# LED_Cube.net
KiCad netlist of a schematic drawn in EAGLE
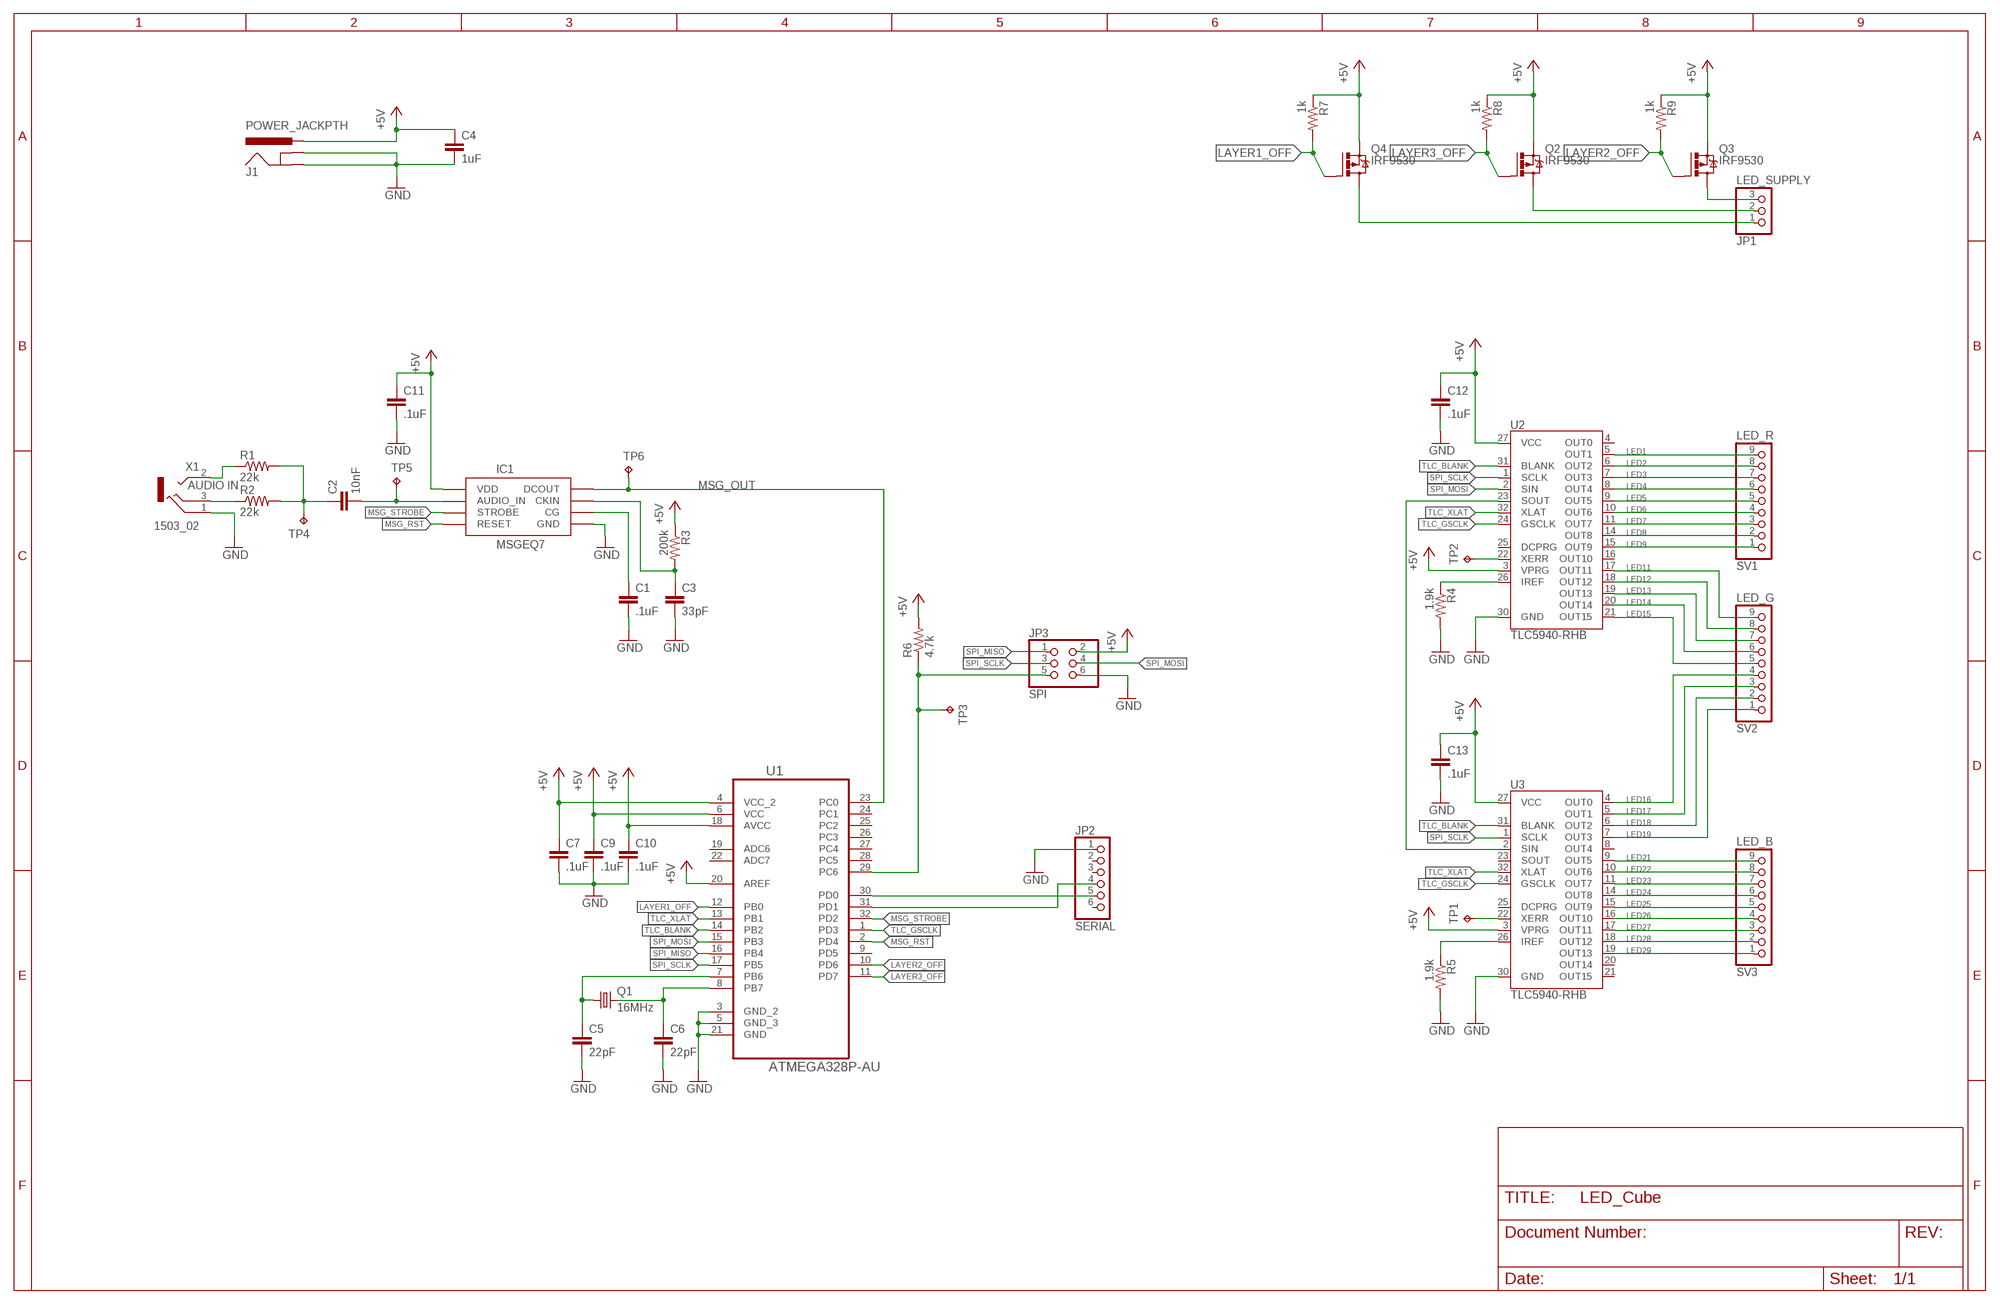
[diagram p0: schematic, sheet 1]

(export (version "E")
  (design (tool "Eeschema 10.0.6"))
  (components
    (comp (ref "C1")
      (value ".1uF")
      (footprint "eagle-import:C0805")
      (libsource (lib "eagle-import") (part "C-EUC0805"))
    )
    (comp (ref "C2")
      (value "10nF")
      (footprint "eagle-import:C0805")
      (libsource (lib "eagle-import") (part "C-EUC0805"))
    )
    (comp (ref "C3")
      (value "33pF")
      (footprint "eagle-import:C0805")
      (libsource (lib "eagle-import") (part "C-EUC0805"))
    )
    (comp (ref "C4")
      (value "1uF")
      (footprint "eagle-import:C0805")
      (libsource (lib "eagle-import") (part "C-EUC0805"))
    )
    (comp (ref "C5")
      (value "22pF")
      (footprint "eagle-import:C0805")
      (libsource (lib "eagle-import") (part "C-EUC0805"))
    )
    (comp (ref "C6")
      (value "22pF")
      (footprint "eagle-import:C0805")
      (libsource (lib "eagle-import") (part "C-EUC0805"))
    )
    (comp (ref "C7")
      (value ".1uF")
      (footprint "eagle-import:C0402")
      (libsource (lib "eagle-import") (part "C-EUC0402"))
    )
    (comp (ref "C9")
      (value ".1uF")
      (footprint "eagle-import:C0402")
      (libsource (lib "eagle-import") (part "C-EUC0402"))
    )
    (comp (ref "C10")
      (value ".1uF")
      (footprint "eagle-import:C0402")
      (libsource (lib "eagle-import") (part "C-EUC0402"))
    )
    (comp (ref "C11")
      (value ".1uF")
      (footprint "eagle-import:C0805")
      (libsource (lib "eagle-import") (part "C-EUC0805"))
    )
    (comp (ref "C12")
      (value ".1uF")
      (footprint "eagle-import:C0402")
      (libsource (lib "eagle-import") (part "C-EUC0402"))
    )
    (comp (ref "C13")
      (value ".1uF")
      (footprint "eagle-import:C0402")
      (libsource (lib "eagle-import") (part "C-EUC0402"))
    )
    (comp (ref "IC1")
      (value "MSGEQ7SOIC")
      (footprint "eagle-import:SOIC8")
      (libsource (lib "eagle-import") (part "MSGEQ7SOIC"))
    )
    (comp (ref "J1")
      (value "POWER_JACKPTH")
      (footprint "eagle-import:POWER_JACK_PTH")
      (libsource (lib "eagle-import") (part "POWER_JACKPTH"))
    )
    (comp (ref "JP1")
      (value "LED_SUPPLY")
      (footprint "eagle-import:1X03")
      (libsource (lib "eagle-import") (part "PINHD-1X3"))
    )
    (comp (ref "JP2")
      (value "SERIAL")
      (footprint "eagle-import:1X06")
      (libsource (lib "eagle-import") (part "PINHD-1X6"))
    )
    (comp (ref "JP3")
      (value "SPI")
      (footprint "eagle-import:2X03")
      (libsource (lib "eagle-import") (part "PINHD-2X3"))
    )
    (comp (ref "Q1")
      (value "16MHz")
      (footprint "eagle-import:HC49UP")
      (libsource (lib "eagle-import") (part "CRYSTALHC49UP"))
    )
    (comp (ref "Q2")
      (value "IRF9530")
      (footprint "eagle-import:TO220BV")
      (libsource (lib "eagle-import") (part "IRF9530"))
    )
    (comp (ref "Q3")
      (value "IRF9530")
      (footprint "eagle-import:TO220BV")
      (libsource (lib "eagle-import") (part "IRF9530"))
    )
    (comp (ref "Q4")
      (value "IRF9530")
      (footprint "eagle-import:TO220BV")
      (libsource (lib "eagle-import") (part "IRF9530"))
    )
    (comp (ref "R1")
      (value "22k")
      (footprint "eagle-import:R0805")
      (libsource (lib "eagle-import") (part "R-US_R0805"))
    )
    (comp (ref "R2")
      (value "22k")
      (footprint "eagle-import:R0805")
      (libsource (lib "eagle-import") (part "R-US_R0805"))
    )
    (comp (ref "R3")
      (value "200k")
      (footprint "eagle-import:R0805")
      (libsource (lib "eagle-import") (part "R-US_R0805"))
    )
    (comp (ref "R4")
      (value "1.9k")
      (footprint "eagle-import:R0402")
      (libsource (lib "eagle-import") (part "R-US_R0402"))
    )
    (comp (ref "R5")
      (value "1.9k")
      (footprint "eagle-import:R0402")
      (libsource (lib "eagle-import") (part "R-US_R0402"))
    )
    (comp (ref "R6")
      (value "4.7k")
      (footprint "eagle-import:R0805")
      (libsource (lib "eagle-import") (part "R-US_R0805"))
    )
    (comp (ref "R7")
      (value "1k")
      (footprint "eagle-import:R0805")
      (libsource (lib "eagle-import") (part "R-US_R0805"))
    )
    (comp (ref "R8")
      (value "1k")
      (footprint "eagle-import:R0805")
      (libsource (lib "eagle-import") (part "R-US_R0805"))
    )
    (comp (ref "R9")
      (value "1k")
      (footprint "eagle-import:R0805")
      (libsource (lib "eagle-import") (part "R-US_R0805"))
    )
    (comp (ref "SV1")
      (value "LED_R")
      (footprint "eagle-import:1X09")
      (libsource (lib "eagle-import") (part "PINHD-1X9"))
    )
    (comp (ref "SV2")
      (value "LED_G")
      (footprint "eagle-import:1X09")
      (libsource (lib "eagle-import") (part "PINHD-1X9"))
    )
    (comp (ref "SV3")
      (value "LED_B")
      (footprint "eagle-import:1X09")
      (libsource (lib "eagle-import") (part "PINHD-1X9"))
    )
    (comp (ref "TP1")
      (value "TPPAD1-13")
      (footprint "eagle-import:P1-13")
      (libsource (lib "eagle-import") (part "TPPAD1-13"))
    )
    (comp (ref "TP2")
      (value "TPPAD1-13")
      (footprint "eagle-import:P1-13")
      (libsource (lib "eagle-import") (part "TPPAD1-13"))
    )
    (comp (ref "TP3")
      (value "TPPAD1-13")
      (footprint "eagle-import:P1-13")
      (libsource (lib "eagle-import") (part "TPPAD1-13"))
    )
    (comp (ref "TP4")
      (value "TPPAD1-13")
      (footprint "eagle-import:P1-13")
      (libsource (lib "eagle-import") (part "TPPAD1-13"))
    )
    (comp (ref "TP5")
      (value "TPPAD1-13")
      (footprint "eagle-import:P1-13")
      (libsource (lib "eagle-import") (part "TPPAD1-13"))
    )
    (comp (ref "TP6")
      (value "TPPAD1-13")
      (footprint "eagle-import:P1-13")
      (libsource (lib "eagle-import") (part "TPPAD1-13"))
    )
    (comp (ref "U1")
      (value "ATMEGA328P-AU")
      (footprint "eagle-import:QFP80P900X900X120-32N")
      (libsource (lib "eagle-import") (part "ATMEGA328P-AU"))
    )
    (comp (ref "U2")
      (value "TLC5940-RHB")
      (footprint "eagle-import:QFN-32")
      (libsource (lib "eagle-import") (part "TLC5940-RHB"))
    )
    (comp (ref "U3")
      (value "TLC5940-RHB")
      (footprint "eagle-import:QFN-32")
      (libsource (lib "eagle-import") (part "TLC5940-RHB"))
    )
    (comp (ref "X1")
      (value "1503_02")
      (footprint "eagle-import:1503_02")
      (libsource (lib "eagle-import") (part "1503_02"))
    )
  )
  (nets
    (net (code "1") (name "+5V") (class "Default")
      (node (ref "C10") (pin "1") (pinfunction "1_1") (pintype "passive"))
      (node (ref "C11") (pin "1") (pinfunction "1_1") (pintype "passive"))
      (node (ref "C12") (pin "1") (pinfunction "1_1") (pintype "passive"))
      (node (ref "C13") (pin "1") (pinfunction "1_1") (pintype "passive"))
      (node (ref "C4") (pin "1") (pinfunction "1_1") (pintype "passive"))
      (node (ref "C7") (pin "1") (pinfunction "1_1") (pintype "passive"))
      (node (ref "C9") (pin "1") (pinfunction "1_1") (pintype "passive"))
      (node (ref "IC1") (pin "1") (pinfunction "VDD_1") (pintype "input"))
      (node (ref "J1") (pin "PWR") (pinfunction "PWR_PWR") (pintype "bidirectional"))
      (node (ref "JP3") (pin "2") (pinfunction "2_2") (pintype "passive"))
      (node (ref "Q2") (pin "S") (pinfunction "S_S") (pintype "passive"))
      (node (ref "Q3") (pin "S") (pinfunction "S_S") (pintype "passive"))
      (node (ref "Q4") (pin "S") (pinfunction "S_S") (pintype "passive"))
      (node (ref "R3") (pin "1") (pinfunction "1_1") (pintype "passive"))
      (node (ref "R6") (pin "2") (pinfunction "2_2") (pintype "passive"))
      (node (ref "R7") (pin "1") (pinfunction "1_1") (pintype "passive"))
      (node (ref "R8") (pin "1") (pinfunction "1_1") (pintype "passive"))
      (node (ref "R9") (pin "1") (pinfunction "1_1") (pintype "passive"))
      (node (ref "U1") (pin "18") (pinfunction "AVCC_18") (pintype "power_in"))
      (node (ref "U1") (pin "20") (pinfunction "AREF_20") (pintype "input"))
      (node (ref "U1") (pin "4") (pinfunction "VCC_2_4") (pintype "power_in"))
      (node (ref "U1") (pin "6") (pinfunction "VCC_6") (pintype "power_in"))
      (node (ref "U2") (pin "27") (pinfunction "VCC_27") (pintype "bidirectional"))
      (node (ref "U2") (pin "3") (pinfunction "VPRG_3") (pintype "bidirectional"))
      (node (ref "U3") (pin "27") (pinfunction "VCC_27") (pintype "bidirectional"))
      (node (ref "U3") (pin "3") (pinfunction "VPRG_3") (pintype "bidirectional"))
    )
    (net (code "2") (name "/LED1") (class "Default")
      (node (ref "SV1") (pin "9") (pinfunction "9_9") (pintype "passive"))
      (node (ref "U2") (pin "5") (pinfunction "OUT1_5") (pintype "bidirectional"))
    )
    (net (code "3") (name "/LED2") (class "Default")
      (node (ref "SV1") (pin "8") (pinfunction "8_8") (pintype "passive"))
      (node (ref "U2") (pin "6") (pinfunction "OUT2_6") (pintype "bidirectional"))
    )
    (net (code "4") (name "/LED3") (class "Default")
      (node (ref "SV1") (pin "7") (pinfunction "7_7") (pintype "passive"))
      (node (ref "U2") (pin "7") (pinfunction "OUT3_7") (pintype "bidirectional"))
    )
    (net (code "5") (name "/LED4") (class "Default")
      (node (ref "SV1") (pin "6") (pinfunction "6_6") (pintype "passive"))
      (node (ref "U2") (pin "8") (pinfunction "OUT4_8") (pintype "bidirectional"))
    )
    (net (code "6") (name "/LED5") (class "Default")
      (node (ref "SV1") (pin "5") (pinfunction "5_5") (pintype "passive"))
      (node (ref "U2") (pin "9") (pinfunction "OUT5_9") (pintype "bidirectional"))
    )
    (net (code "7") (name "/LED6") (class "Default")
      (node (ref "SV1") (pin "4") (pinfunction "4_4") (pintype "passive"))
      (node (ref "U2") (pin "10") (pinfunction "OUT6_10") (pintype "bidirectional"))
    )
    (net (code "8") (name "/LED7") (class "Default")
      (node (ref "SV1") (pin "3") (pinfunction "3_3") (pintype "passive"))
      (node (ref "U2") (pin "11") (pinfunction "OUT7_11") (pintype "bidirectional"))
    )
    (net (code "9") (name "/LED8") (class "Default")
      (node (ref "SV1") (pin "2") (pinfunction "2_2") (pintype "passive"))
      (node (ref "U2") (pin "14") (pinfunction "OUT8_14") (pintype "bidirectional"))
    )
    (net (code "10") (name "/LED9") (class "Default")
      (node (ref "SV1") (pin "1") (pinfunction "1_1") (pintype "passive"))
      (node (ref "U2") (pin "15") (pinfunction "OUT9_15") (pintype "bidirectional"))
    )
    (net (code "11") (name "/LED11") (class "Default")
      (node (ref "SV2") (pin "9") (pinfunction "9_9") (pintype "passive"))
      (node (ref "U2") (pin "17") (pinfunction "OUT11_17") (pintype "bidirectional"))
    )
    (net (code "12") (name "/LED12") (class "Default")
      (node (ref "SV2") (pin "8") (pinfunction "8_8") (pintype "passive"))
      (node (ref "U2") (pin "18") (pinfunction "OUT12_18") (pintype "bidirectional"))
    )
    (net (code "13") (name "/LED13") (class "Default")
      (node (ref "SV2") (pin "7") (pinfunction "7_7") (pintype "passive"))
      (node (ref "U2") (pin "19") (pinfunction "OUT13_19") (pintype "bidirectional"))
    )
    (net (code "14") (name "/LED14") (class "Default")
      (node (ref "SV2") (pin "6") (pinfunction "6_6") (pintype "passive"))
      (node (ref "U2") (pin "20") (pinfunction "OUT14_20") (pintype "bidirectional"))
    )
    (net (code "15") (name "/LED15") (class "Default")
      (node (ref "SV2") (pin "5") (pinfunction "5_5") (pintype "passive"))
      (node (ref "U2") (pin "21") (pinfunction "OUT15_21") (pintype "bidirectional"))
    )
    (net (code "16") (name "/LED16") (class "Default")
      (node (ref "SV2") (pin "4") (pinfunction "4_4") (pintype "passive"))
      (node (ref "U3") (pin "4") (pinfunction "OUT0_4") (pintype "bidirectional"))
    )
    (net (code "17") (name "/LED17") (class "Default")
      (node (ref "SV2") (pin "3") (pinfunction "3_3") (pintype "passive"))
      (node (ref "U3") (pin "5") (pinfunction "OUT1_5") (pintype "bidirectional"))
    )
    (net (code "18") (name "/LED18") (class "Default")
      (node (ref "SV2") (pin "2") (pinfunction "2_2") (pintype "passive"))
      (node (ref "U3") (pin "6") (pinfunction "OUT2_6") (pintype "bidirectional"))
    )
    (net (code "19") (name "/LED19") (class "Default")
      (node (ref "SV2") (pin "1") (pinfunction "1_1") (pintype "passive"))
      (node (ref "U3") (pin "7") (pinfunction "OUT3_7") (pintype "bidirectional"))
    )
    (net (code "20") (name "/LED21") (class "Default")
      (node (ref "SV3") (pin "9") (pinfunction "9_9") (pintype "passive"))
      (node (ref "U3") (pin "9") (pinfunction "OUT5_9") (pintype "bidirectional"))
    )
    (net (code "21") (name "/LED22") (class "Default")
      (node (ref "SV3") (pin "8") (pinfunction "8_8") (pintype "passive"))
      (node (ref "U3") (pin "10") (pinfunction "OUT6_10") (pintype "bidirectional"))
    )
    (net (code "22") (name "/LED23") (class "Default")
      (node (ref "SV3") (pin "7") (pinfunction "7_7") (pintype "passive"))
      (node (ref "U3") (pin "11") (pinfunction "OUT7_11") (pintype "bidirectional"))
    )
    (net (code "23") (name "/LED24") (class "Default")
      (node (ref "SV3") (pin "6") (pinfunction "6_6") (pintype "passive"))
      (node (ref "U3") (pin "14") (pinfunction "OUT8_14") (pintype "bidirectional"))
    )
    (net (code "24") (name "/LED25") (class "Default")
      (node (ref "SV3") (pin "5") (pinfunction "5_5") (pintype "passive"))
      (node (ref "U3") (pin "15") (pinfunction "OUT9_15") (pintype "bidirectional"))
    )
    (net (code "25") (name "/LED26") (class "Default")
      (node (ref "SV3") (pin "4") (pinfunction "4_4") (pintype "passive"))
      (node (ref "U3") (pin "16") (pinfunction "OUT10_16") (pintype "bidirectional"))
    )
    (net (code "26") (name "/LED27") (class "Default")
      (node (ref "SV3") (pin "3") (pinfunction "3_3") (pintype "passive"))
      (node (ref "U3") (pin "17") (pinfunction "OUT11_17") (pintype "bidirectional"))
    )
    (net (code "27") (name "/LED28") (class "Default")
      (node (ref "SV3") (pin "2") (pinfunction "2_2") (pintype "passive"))
      (node (ref "U3") (pin "18") (pinfunction "OUT12_18") (pintype "bidirectional"))
    )
    (net (code "28") (name "/LED29") (class "Default")
      (node (ref "SV3") (pin "1") (pinfunction "1_1") (pintype "passive"))
      (node (ref "U3") (pin "19") (pinfunction "OUT13_19") (pintype "bidirectional"))
    )
    (net (code "29") (name "/MSG_OUT") (class "Default")
      (node (ref "IC1") (pin "3") (pinfunction "DCOUT_3") (pintype "bidirectional"))
      (node (ref "TP6") (pin "TP") (pinfunction "TP_TP") (pintype "input"))
      (node (ref "U1") (pin "23") (pinfunction "PC0_23") (pintype "bidirectional"))
    )
    (net (code "30") (name "GND") (class "Default")
      (node (ref "C1") (pin "2") (pinfunction "2_2") (pintype "passive"))
      (node (ref "C10") (pin "2") (pinfunction "2_2") (pintype "passive"))
      (node (ref "C11") (pin "2") (pinfunction "2_2") (pintype "passive"))
      (node (ref "C12") (pin "2") (pinfunction "2_2") (pintype "passive"))
      (node (ref "C13") (pin "2") (pinfunction "2_2") (pintype "passive"))
      (node (ref "C3") (pin "2") (pinfunction "2_2") (pintype "passive"))
      (node (ref "C4") (pin "2") (pinfunction "2_2") (pintype "passive"))
      (node (ref "C5") (pin "2") (pinfunction "2_2") (pintype "passive"))
      (node (ref "C6") (pin "2") (pinfunction "2_2") (pintype "passive"))
      (node (ref "C7") (pin "2") (pinfunction "2_2") (pintype "passive"))
      (node (ref "C9") (pin "2") (pinfunction "2_2") (pintype "passive"))
      (node (ref "IC1") (pin "2") (pinfunction "GND_2") (pintype "bidirectional"))
      (node (ref "J1") (pin "GND") (pinfunction "GND_GND") (pintype "bidirectional"))
      (node (ref "J1") (pin "GNDBREAK") (pinfunction "GNDBREAK_GNDBREAK") (pintype "bidirectional"))
      (node (ref "JP2") (pin "1") (pinfunction "1_1") (pintype "passive"))
      (node (ref "JP3") (pin "6") (pinfunction "6_6") (pintype "passive"))
      (node (ref "R4") (pin "2") (pinfunction "2_2") (pintype "passive"))
      (node (ref "R5") (pin "2") (pinfunction "2_2") (pintype "passive"))
      (node (ref "U1") (pin "21") (pinfunction "GND_21") (pintype "passive"))
      (node (ref "U1") (pin "3") (pinfunction "GND_2_3") (pintype "passive"))
      (node (ref "U1") (pin "5") (pinfunction "GND_3_5") (pintype "passive"))
      (node (ref "U2") (pin "30") (pinfunction "GND_30") (pintype "bidirectional"))
      (node (ref "U3") (pin "30") (pinfunction "GND_30") (pintype "bidirectional"))
      (node (ref "X1") (pin "1") (pinfunction "1_1") (pintype "passive"))
    )
    (net (code "31") (name "LAYER1_OFF") (class "Default")
      (node (ref "Q4") (pin "G") (pinfunction "G_G") (pintype "passive"))
      (node (ref "R7") (pin "2") (pinfunction "2_2") (pintype "passive"))
      (node (ref "U1") (pin "12") (pinfunction "PB0_12") (pintype "bidirectional"))
    )
    (net (code "32") (name "LAYER2_OFF") (class "Default")
      (node (ref "Q3") (pin "G") (pinfunction "G_G") (pintype "passive"))
      (node (ref "R9") (pin "2") (pinfunction "2_2") (pintype "passive"))
      (node (ref "U1") (pin "10") (pinfunction "PD6_10") (pintype "bidirectional"))
    )
    (net (code "33") (name "LAYER3_OFF") (class "Default")
      (node (ref "Q2") (pin "G") (pinfunction "G_G") (pintype "passive"))
      (node (ref "R8") (pin "2") (pinfunction "2_2") (pintype "passive"))
      (node (ref "U1") (pin "11") (pinfunction "PD7_11") (pintype "bidirectional"))
    )
    (net (code "34") (name "MSG_RST") (class "Default")
      (node (ref "IC1") (pin "7") (pinfunction "RESET_7") (pintype "input"))
      (node (ref "U1") (pin "2") (pinfunction "PD4_2") (pintype "bidirectional"))
    )
    (net (code "35") (name "MSG_STROBE") (class "Default")
      (node (ref "IC1") (pin "4") (pinfunction "STROBE_4") (pintype "input"))
      (node (ref "U1") (pin "32") (pinfunction "PD2_32") (pintype "bidirectional"))
    )
    (net (code "36") (name "Net-(C2-Pad1)") (class "Default")
      (node (ref "C2") (pin "1") (pinfunction "1_1") (pintype "passive"))
      (node (ref "R1") (pin "2") (pinfunction "2_2") (pintype "passive"))
      (node (ref "R2") (pin "2") (pinfunction "2_2") (pintype "passive"))
      (node (ref "TP4") (pin "TP") (pinfunction "TP_TP") (pintype "input"))
    )
    (net (code "37") (name "Net-(IC1-AUDIO_IN)") (class "Default")
      (node (ref "C2") (pin "2") (pinfunction "2_2") (pintype "passive"))
      (node (ref "IC1") (pin "5") (pinfunction "AUDIO_IN_5") (pintype "input"))
      (node (ref "TP5") (pin "TP") (pinfunction "TP_TP") (pintype "input"))
    )
    (net (code "38") (name "Net-(IC1-CG)") (class "Default")
      (node (ref "C1") (pin "1") (pinfunction "1_1") (pintype "passive"))
      (node (ref "IC1") (pin "6") (pinfunction "CG_6") (pintype "bidirectional"))
    )
    (net (code "39") (name "Net-(IC1-CKIN)") (class "Default")
      (node (ref "C3") (pin "1") (pinfunction "1_1") (pintype "passive"))
      (node (ref "IC1") (pin "8") (pinfunction "CKIN_8") (pintype "bidirectional"))
      (node (ref "R3") (pin "2") (pinfunction "2_2") (pintype "passive"))
    )
    (net (code "40") (name "Net-(JP1-Pad1)") (class "Default")
      (node (ref "JP1") (pin "1") (pinfunction "1_1") (pintype "passive"))
      (node (ref "Q4") (pin "D") (pinfunction "D_D") (pintype "passive"))
    )
    (net (code "41") (name "Net-(JP1-Pad2)") (class "Default")
      (node (ref "JP1") (pin "2") (pinfunction "2_2") (pintype "passive"))
      (node (ref "Q2") (pin "D") (pinfunction "D_D") (pintype "passive"))
    )
    (net (code "42") (name "Net-(JP1-Pad3)") (class "Default")
      (node (ref "JP1") (pin "3") (pinfunction "3_3") (pintype "passive"))
      (node (ref "Q3") (pin "D") (pinfunction "D_D") (pintype "passive"))
    )
    (net (code "43") (name "Net-(R1-Pad1)") (class "Default")
      (node (ref "R1") (pin "1") (pinfunction "1_1") (pintype "passive"))
      (node (ref "X1") (pin "2") (pinfunction "2_2") (pintype "passive"))
    )
    (net (code "44") (name "Net-(R2-Pad1)") (class "Default")
      (node (ref "R2") (pin "1") (pinfunction "1_1") (pintype "passive"))
      (node (ref "X1") (pin "3") (pinfunction "3_3") (pintype "passive"))
    )
    (net (code "45") (name "Net-(U1-PB6)") (class "Default")
      (node (ref "C5") (pin "1") (pinfunction "1_1") (pintype "passive"))
      (node (ref "Q1") (pin "1") (pinfunction "1_1") (pintype "passive"))
      (node (ref "U1") (pin "7") (pinfunction "PB6_7") (pintype "bidirectional"))
    )
    (net (code "46") (name "Net-(U1-PB7)") (class "Default")
      (node (ref "C6") (pin "1") (pinfunction "1_1") (pintype "passive"))
      (node (ref "Q1") (pin "2") (pinfunction "2_2") (pintype "passive"))
      (node (ref "U1") (pin "8") (pinfunction "PB7_8") (pintype "bidirectional"))
    )
    (net (code "47") (name "Net-(U1-PC6)") (class "Default")
      (node (ref "JP3") (pin "5") (pinfunction "5_5") (pintype "passive"))
      (node (ref "R6") (pin "1") (pinfunction "1_1") (pintype "passive"))
      (node (ref "TP3") (pin "TP") (pinfunction "TP_TP") (pintype "input"))
      (node (ref "U1") (pin "29") (pinfunction "PC6_29") (pintype "bidirectional"))
    )
    (net (code "48") (name "Net-(U1-PD0)") (class "Default")
      (node (ref "JP2") (pin "5") (pinfunction "5_5") (pintype "passive"))
      (node (ref "U1") (pin "30") (pinfunction "PD0_30") (pintype "bidirectional"))
    )
    (net (code "49") (name "Net-(U1-PD1)") (class "Default")
      (node (ref "JP2") (pin "4") (pinfunction "4_4") (pintype "passive"))
      (node (ref "U1") (pin "31") (pinfunction "PD1_31") (pintype "bidirectional"))
    )
    (net (code "50") (name "Net-(U2-IREF)") (class "Default")
      (node (ref "R4") (pin "1") (pinfunction "1_1") (pintype "passive"))
      (node (ref "U2") (pin "26") (pinfunction "IREF_26") (pintype "bidirectional"))
    )
    (net (code "51") (name "Net-(U2-SOUT)") (class "Default")
      (node (ref "U2") (pin "23") (pinfunction "SOUT_23") (pintype "bidirectional"))
      (node (ref "U3") (pin "2") (pinfunction "SIN_2") (pintype "bidirectional"))
    )
    (net (code "52") (name "Net-(U2-XERR)") (class "Default")
      (node (ref "TP2") (pin "TP") (pinfunction "TP_TP") (pintype "input"))
      (node (ref "U2") (pin "22") (pinfunction "XERR_22") (pintype "bidirectional"))
    )
    (net (code "53") (name "Net-(U3-IREF)") (class "Default")
      (node (ref "R5") (pin "1") (pinfunction "1_1") (pintype "passive"))
      (node (ref "U3") (pin "26") (pinfunction "IREF_26") (pintype "bidirectional"))
    )
    (net (code "54") (name "Net-(U3-XERR)") (class "Default")
      (node (ref "TP1") (pin "TP") (pinfunction "TP_TP") (pintype "input"))
      (node (ref "U3") (pin "22") (pinfunction "XERR_22") (pintype "bidirectional"))
    )
    (net (code "55") (name "SPI_MISO") (class "Default")
      (node (ref "JP3") (pin "1") (pinfunction "1_1") (pintype "passive"))
      (node (ref "U1") (pin "16") (pinfunction "PB4_16") (pintype "bidirectional"))
    )
    (net (code "56") (name "SPI_MOSI") (class "Default")
      (node (ref "JP3") (pin "4") (pinfunction "4_4") (pintype "passive"))
      (node (ref "U1") (pin "15") (pinfunction "PB3_15") (pintype "bidirectional"))
      (node (ref "U2") (pin "2") (pinfunction "SIN_2") (pintype "bidirectional"))
    )
    (net (code "57") (name "SPI_SCLK") (class "Default")
      (node (ref "JP3") (pin "3") (pinfunction "3_3") (pintype "passive"))
      (node (ref "U1") (pin "17") (pinfunction "PB5_17") (pintype "bidirectional"))
      (node (ref "U2") (pin "1") (pinfunction "SCLK_1") (pintype "bidirectional"))
      (node (ref "U3") (pin "1") (pinfunction "SCLK_1") (pintype "bidirectional"))
    )
    (net (code "58") (name "TLC_BLANK") (class "Default")
      (node (ref "U1") (pin "14") (pinfunction "PB2_14") (pintype "bidirectional"))
      (node (ref "U2") (pin "31") (pinfunction "BLANK_31") (pintype "bidirectional"))
      (node (ref "U3") (pin "31") (pinfunction "BLANK_31") (pintype "bidirectional"))
    )
    (net (code "59") (name "TLC_GSCLK") (class "Default")
      (node (ref "U1") (pin "1") (pinfunction "PD3_1") (pintype "bidirectional"))
      (node (ref "U2") (pin "24") (pinfunction "GSCLK_24") (pintype "bidirectional"))
      (node (ref "U3") (pin "24") (pinfunction "GSCLK_24") (pintype "bidirectional"))
    )
    (net (code "60") (name "TLC_XLAT") (class "Default")
      (node (ref "U1") (pin "13") (pinfunction "PB1_13") (pintype "bidirectional"))
      (node (ref "U2") (pin "32") (pinfunction "XLAT_32") (pintype "bidirectional"))
      (node (ref "U3") (pin "32") (pinfunction "XLAT_32") (pintype "bidirectional"))
    )
    (net (code "61") (name "unconnected-(JP2-Pad2)") (class "Default")
      (node (ref "JP2") (pin "2") (pinfunction "2_2") (pintype "passive"))
    )
    (net (code "62") (name "unconnected-(JP2-Pad3)") (class "Default")
      (node (ref "JP2") (pin "3") (pinfunction "3_3") (pintype "passive"))
    )
    (net (code "63") (name "unconnected-(JP2-Pad6)") (class "Default")
      (node (ref "JP2") (pin "6") (pinfunction "6_6") (pintype "passive"))
    )
    (net (code "64") (name "unconnected-(U1-ADC6-Pad19)") (class "Default")
      (node (ref "U1") (pin "19") (pinfunction "ADC6_19") (pintype "input"))
    )
    (net (code "65") (name "unconnected-(U1-ADC7-Pad22)") (class "Default")
      (node (ref "U1") (pin "22") (pinfunction "ADC7_22") (pintype "input"))
    )
    (net (code "66") (name "unconnected-(U1-PC1-Pad24)") (class "Default")
      (node (ref "U1") (pin "24") (pinfunction "PC1_24") (pintype "bidirectional"))
    )
    (net (code "67") (name "unconnected-(U1-PC2-Pad25)") (class "Default")
      (node (ref "U1") (pin "25") (pinfunction "PC2_25") (pintype "bidirectional"))
    )
    (net (code "68") (name "unconnected-(U1-PC3-Pad26)") (class "Default")
      (node (ref "U1") (pin "26") (pinfunction "PC3_26") (pintype "bidirectional"))
    )
    (net (code "69") (name "unconnected-(U1-PC4-Pad27)") (class "Default")
      (node (ref "U1") (pin "27") (pinfunction "PC4_27") (pintype "bidirectional"))
    )
    (net (code "70") (name "unconnected-(U1-PC5-Pad28)") (class "Default")
      (node (ref "U1") (pin "28") (pinfunction "PC5_28") (pintype "bidirectional"))
    )
    (net (code "71") (name "unconnected-(U1-PD5-Pad9)") (class "Default")
      (node (ref "U1") (pin "9") (pinfunction "PD5_9") (pintype "bidirectional"))
    )
    (net (code "72") (name "unconnected-(U2-DCPRG-Pad25)") (class "Default")
      (node (ref "U2") (pin "25") (pinfunction "DCPRG_25") (pintype "bidirectional"))
    )
    (net (code "73") (name "unconnected-(U2-OUT0-Pad4)") (class "Default")
      (node (ref "U2") (pin "4") (pinfunction "OUT0_4") (pintype "bidirectional"))
    )
    (net (code "74") (name "unconnected-(U2-OUT10-Pad16)") (class "Default")
      (node (ref "U2") (pin "16") (pinfunction "OUT10_16") (pintype "bidirectional"))
    )
    (net (code "75") (name "unconnected-(U3-DCPRG-Pad25)") (class "Default")
      (node (ref "U3") (pin "25") (pinfunction "DCPRG_25") (pintype "bidirectional"))
    )
    (net (code "76") (name "unconnected-(U3-OUT4-Pad8)") (class "Default")
      (node (ref "U3") (pin "8") (pinfunction "OUT4_8") (pintype "bidirectional"))
    )
    (net (code "77") (name "unconnected-(U3-OUT14-Pad20)") (class "Default")
      (node (ref "U3") (pin "20") (pinfunction "OUT14_20") (pintype "bidirectional"))
    )
    (net (code "78") (name "unconnected-(U3-OUT15-Pad21)") (class "Default")
      (node (ref "U3") (pin "21") (pinfunction "OUT15_21") (pintype "bidirectional"))
    )
    (net (code "79") (name "unconnected-(U3-SOUT-Pad23)") (class "Default")
      (node (ref "U3") (pin "23") (pinfunction "SOUT_23") (pintype "bidirectional"))
    )
    (net (code "80") (name "unconnected-(X1-2-Pad2@2)") (class "Default")
      (node (ref "X1") (pin "2@2") (pinfunction "2_2@2") (pintype "passive"))
    )
  )
)
